# BLDController_v1_0.net
KiCad netlist of a schematic drawn in EAGLE
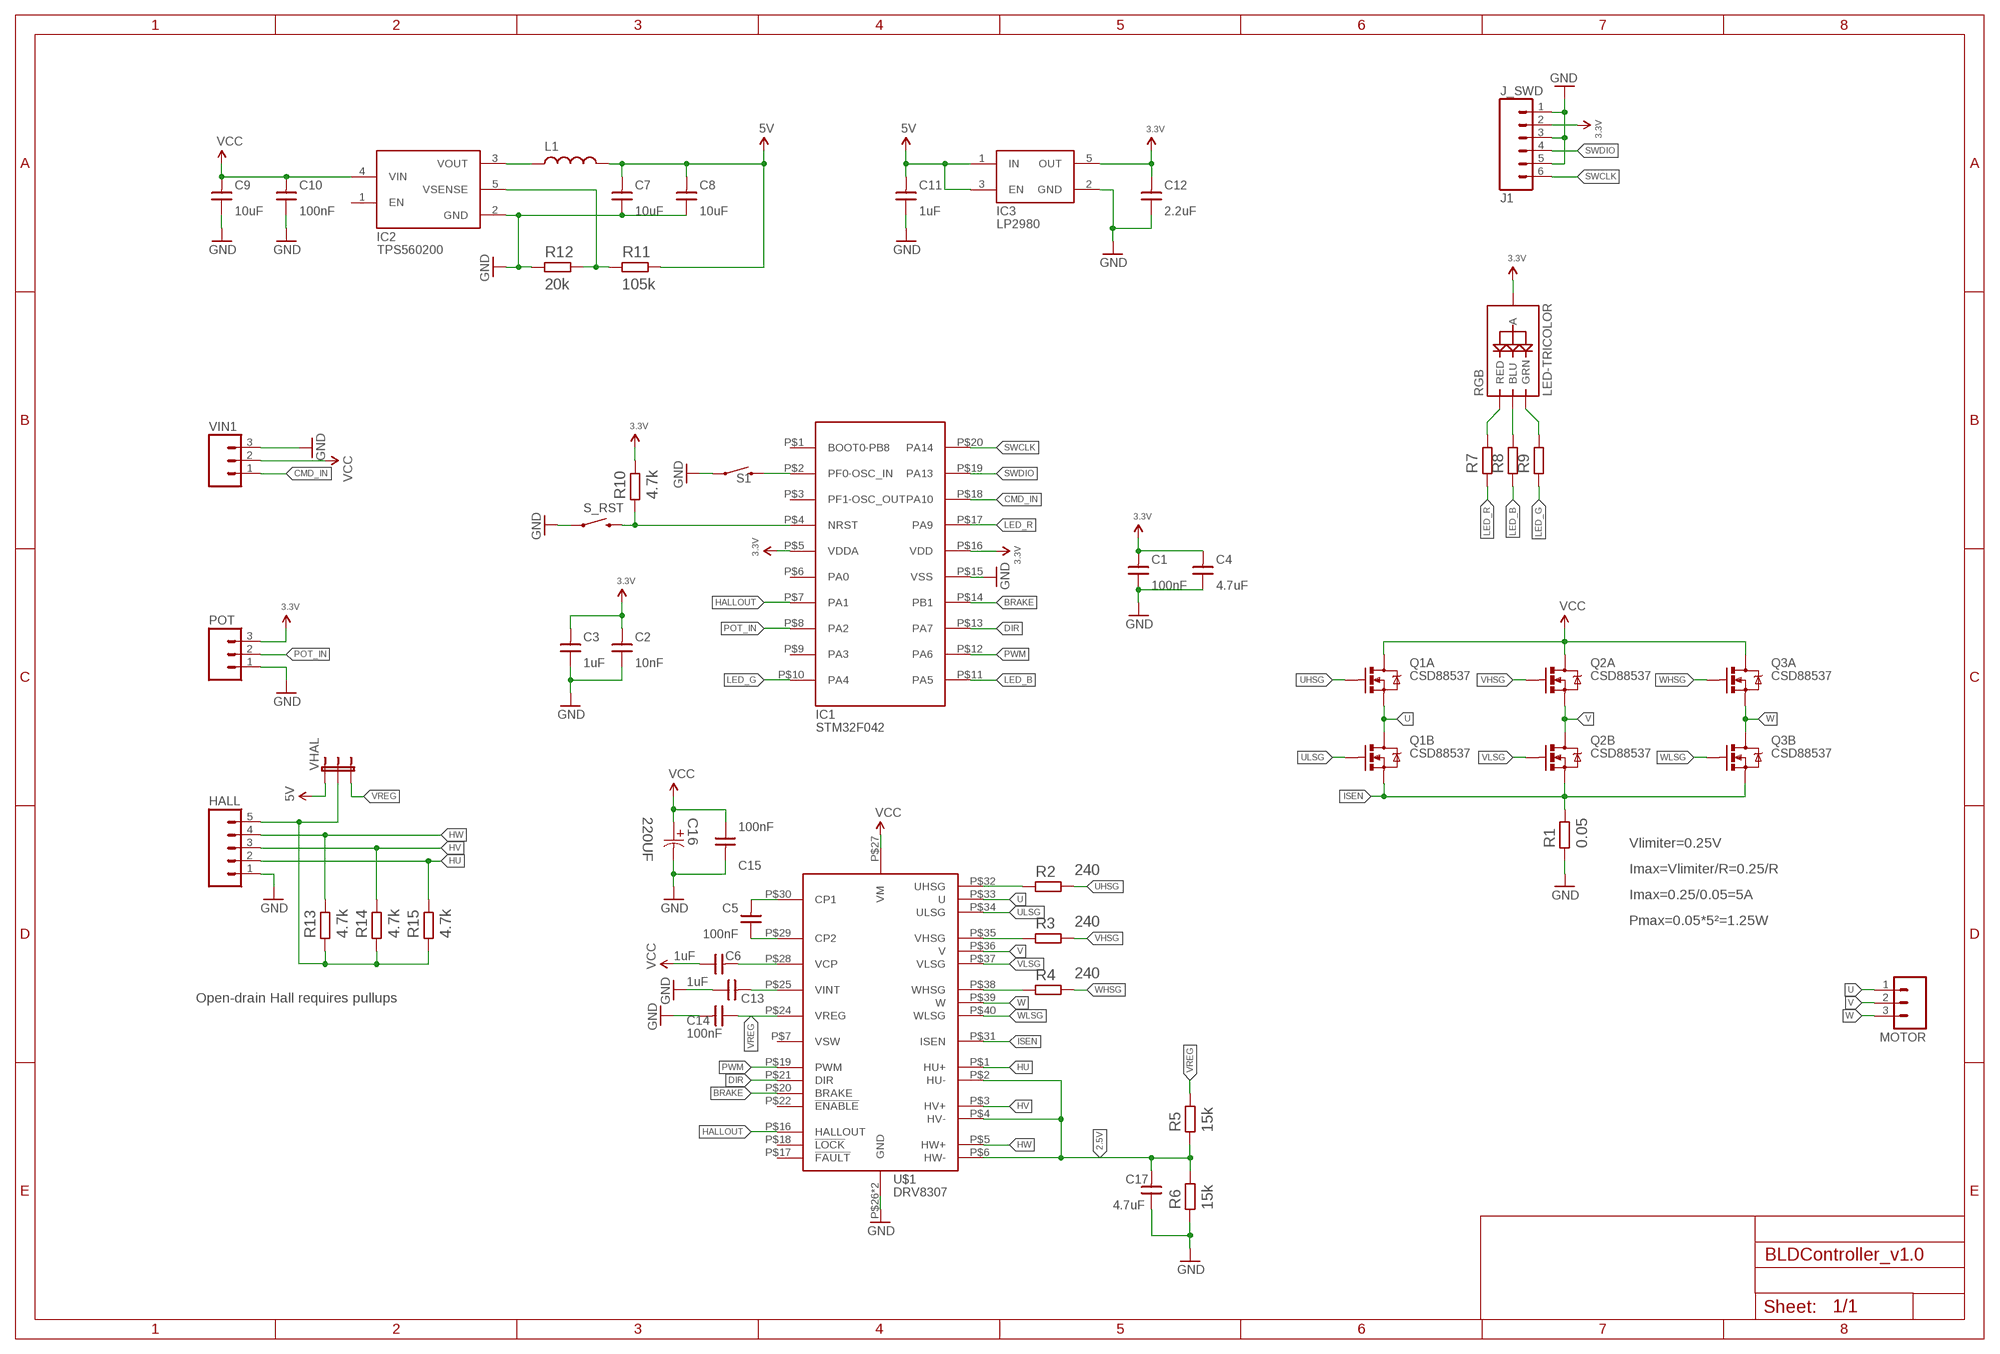
[diagram p0: schematic, sheet 1]

(export (version "E")
  (design (tool "Eeschema 10.0.6"))
  (components
    (comp (ref "C1")
      (value "100nF")
      (footprint "eagle-import:R0603")
      (libsource (lib "eagle-import") (part "C0603"))
    )
    (comp (ref "C2")
      (value "10nF")
      (footprint "eagle-import:R0603")
      (libsource (lib "eagle-import") (part "C0603"))
    )
    (comp (ref "C3")
      (value "1uF")
      (footprint "eagle-import:R0805")
      (libsource (lib "eagle-import") (part "C0805"))
    )
    (comp (ref "C4")
      (value "4.7uF")
      (footprint "eagle-import:R0805")
      (libsource (lib "eagle-import") (part "C0805"))
    )
    (comp (ref "C5")
      (value "100nF")
      (footprint "eagle-import:R0603")
      (libsource (lib "eagle-import") (part "C0603"))
    )
    (comp (ref "C6")
      (value "1uF")
      (footprint "eagle-import:R0805")
      (libsource (lib "eagle-import") (part "C0805"))
    )
    (comp (ref "C7")
      (value "10uF")
      (footprint "eagle-import:R0805")
      (libsource (lib "eagle-import") (part "C0805"))
    )
    (comp (ref "C8")
      (value "10uF")
      (footprint "eagle-import:R0805")
      (libsource (lib "eagle-import") (part "C0805"))
    )
    (comp (ref "C9")
      (value "10uF")
      (footprint "eagle-import:1206")
      (libsource (lib "eagle-import") (part "C1206"))
    )
    (comp (ref "C10")
      (value "100nF")
      (footprint "eagle-import:R0603")
      (libsource (lib "eagle-import") (part "C0603"))
    )
    (comp (ref "C11")
      (value "1uF")
      (footprint "eagle-import:R0805")
      (libsource (lib "eagle-import") (part "C0805"))
    )
    (comp (ref "C12")
      (value "2.2uF")
      (footprint "eagle-import:R0805")
      (libsource (lib "eagle-import") (part "C0805"))
    )
    (comp (ref "C13")
      (value "1uF")
      (footprint "eagle-import:R0805")
      (libsource (lib "eagle-import") (part "C0805"))
    )
    (comp (ref "C14")
      (value "100nF")
      (footprint "eagle-import:R0603")
      (libsource (lib "eagle-import") (part "C0603"))
    )
    (comp (ref "C15")
      (value "100nF")
      (footprint "eagle-import:R0603")
      (libsource (lib "eagle-import") (part "C0603"))
    )
    (comp (ref "C16")
      (value "220UF")
      (footprint "eagle-import:CAPPR500-1000X3200")
      (fields (field (name "MPN") "EEUFC1V221") (field (name "TOLERANCE") "±20 %"))
      (libsource (lib "eagle-import") (part "C_PANA-P5.0-D10FC1V221"))
    )
    (comp (ref "C17")
      (value "4.7uF")
      (footprint "eagle-import:R0603")
      (libsource (lib "eagle-import") (part "C0603"))
    )
    (comp (ref "HALL")
      (value "M05SCREW")
      (footprint "eagle-import:SCREWTERMINAL-3.5MM-5")
      (libsource (lib "eagle-import") (part "M05SCREW"))
    )
    (comp (ref "IC1")
      (value "STM32F042")
      (footprint "eagle-import:TSSOP20")
      (libsource (lib "eagle-import") (part "STM32F042"))
    )
    (comp (ref "IC2")
      (value "TPS560200")
      (footprint "eagle-import:SOT23-5L")
      (libsource (lib "eagle-import") (part "TPS560200"))
    )
    (comp (ref "IC3")
      (value "LP2980")
      (footprint "eagle-import:SOT23-5L")
      (libsource (lib "eagle-import") (part "LP2980"))
    )
    (comp (ref "J1")
      (value "J_SWD")
      (footprint "eagle-import:ZIF-06-1MM")
      (libsource (lib "eagle-import") (part "ZIF-06-1MM"))
    )
    (comp (ref "L1")
      (value "LNRG_4026")
      (footprint "eagle-import:NRG_4026")
      (libsource (lib "eagle-import") (part "LNRG_4026"))
    )
    (comp (ref "MOTOR")
      (value "M03-SCREW-5MM")
      (footprint "eagle-import:SCREWTERMINAL-5MM-3")
      (libsource (lib "eagle-import") (part "M03-SCREW-5MM"))
    )
    (comp (ref "POT")
      (value "M03SCREW")
      (footprint "eagle-import:SCREWTERMINAL-3.5MM-3")
      (libsource (lib "eagle-import") (part "M03SCREW"))
    )
    (comp (ref "Q1")
      (value "CSD88537")
      (footprint "eagle-import:SO-08")
      (libsource (lib "eagle-import") (part "CSD88537"))
    )
    (comp (ref "Q2")
      (value "CSD88537")
      (footprint "eagle-import:SO-08")
      (libsource (lib "eagle-import") (part "CSD88537"))
    )
    (comp (ref "Q3")
      (value "CSD88537")
      (footprint "eagle-import:SO-08")
      (libsource (lib "eagle-import") (part "CSD88537"))
    )
    (comp (ref "R1")
      (value "0.05")
      (footprint "eagle-import:CRF2512")
      (libsource (lib "eagle-import") (part "R2512"))
    )
    (comp (ref "R2")
      (value "240")
      (footprint "eagle-import:R0603")
      (libsource (lib "eagle-import") (part "R0603"))
    )
    (comp (ref "R3")
      (value "240")
      (footprint "eagle-import:R0603")
      (libsource (lib "eagle-import") (part "R0603"))
    )
    (comp (ref "R4")
      (value "240")
      (footprint "eagle-import:R0603")
      (libsource (lib "eagle-import") (part "R0603"))
    )
    (comp (ref "R5")
      (value "15k")
      (footprint "eagle-import:R0603")
      (libsource (lib "eagle-import") (part "R0603"))
    )
    (comp (ref "R6")
      (value "15k")
      (footprint "eagle-import:R0603")
      (libsource (lib "eagle-import") (part "R0603"))
    )
    (comp (ref "R7")
      (value "R0603")
      (footprint "eagle-import:R0603")
      (libsource (lib "eagle-import") (part "R0603"))
    )
    (comp (ref "R8")
      (value "R0603")
      (footprint "eagle-import:R0603")
      (libsource (lib "eagle-import") (part "R0603"))
    )
    (comp (ref "R9")
      (value "R0603")
      (footprint "eagle-import:R0603")
      (libsource (lib "eagle-import") (part "R0603"))
    )
    (comp (ref "R10")
      (value "4.7k")
      (footprint "eagle-import:R0603")
      (libsource (lib "eagle-import") (part "R0603"))
    )
    (comp (ref "R11")
      (value "105k")
      (footprint "eagle-import:R0603")
      (libsource (lib "eagle-import") (part "R0603"))
    )
    (comp (ref "R12")
      (value "20k")
      (footprint "eagle-import:R0603")
      (libsource (lib "eagle-import") (part "R0603"))
    )
    (comp (ref "R13")
      (value "4.7k")
      (footprint "eagle-import:R0603")
      (libsource (lib "eagle-import") (part "R0603"))
    )
    (comp (ref "R14")
      (value "4.7k")
      (footprint "eagle-import:R0603")
      (libsource (lib "eagle-import") (part "R0603"))
    )
    (comp (ref "R15")
      (value "4.7k")
      (footprint "eagle-import:R0603")
      (libsource (lib "eagle-import") (part "R0603"))
    )
    (comp (ref "RGB")
      (value "LED-TRICOLOR")
      (footprint "eagle-import:PLCC4")
      (libsource (lib "eagle-import") (part "LED-TRICOLOR"))
    )
    (comp (ref "S1")
      (value "SWITCH-MOMENTARY-2SMD-3")
      (footprint "eagle-import:TACTILE_SWITCH_SMD-3")
      (libsource (lib "eagle-import") (part "SWITCH-MOMENTARY-2SMD-3"))
    )
    (comp (ref "S_RST")
      (value "SWITCH-MOMENTARY-2SMD-3")
      (footprint "eagle-import:TACTILE_SWITCH_SMD-3")
      (libsource (lib "eagle-import") (part "SWITCH-MOMENTARY-2SMD-3"))
    )
    (comp (ref "U$1")
      (value "DRV8307")
      (footprint "eagle-import:PVQFN-N40")
      (libsource (lib "eagle-import") (part "DRV8307"))
    )
    (comp (ref "VHAL")
      (value "JUMPER-3SMD")
      (footprint "eagle-import:SJ_3")
      (libsource (lib "eagle-import") (part "JUMPER-3SMD"))
    )
    (comp (ref "VIN1")
      (value "M03SCREW")
      (footprint "eagle-import:SCREWTERMINAL-3.5MM-3")
      (libsource (lib "eagle-import") (part "M03SCREW"))
    )
  )
  (nets
    (net (code "1") (name "2.5V") (class "Default")
      (node (ref "C17") (pin "2") (pinfunction "2_2") (pintype "bidirectional"))
      (node (ref "R5") (pin "1") (pinfunction "1_1") (pintype "bidirectional"))
      (node (ref "R6") (pin "2") (pinfunction "2_2") (pintype "bidirectional"))
      (node (ref "U$1") (pin "P$2") (pinfunction "HU-_P$2") (pintype "bidirectional"))
      (node (ref "U$1") (pin "P$4") (pinfunction "HV-_P$4") (pintype "bidirectional"))
      (node (ref "U$1") (pin "P$6") (pinfunction "HW-_P$6") (pintype "bidirectional"))
    )
    (net (code "2") (name "3.3V") (class "Default")
      (node (ref "C1") (pin "2") (pinfunction "2_2") (pintype "bidirectional"))
      (node (ref "C12") (pin "2") (pinfunction "2_2") (pintype "bidirectional"))
      (node (ref "C2") (pin "2") (pinfunction "2_2") (pintype "bidirectional"))
      (node (ref "C3") (pin "2") (pinfunction "2_2") (pintype "bidirectional"))
      (node (ref "C4") (pin "2") (pinfunction "2_2") (pintype "bidirectional"))
      (node (ref "IC1") (pin "P$16") (pinfunction "VDD_P$16") (pintype "bidirectional"))
      (node (ref "IC1") (pin "P$5") (pinfunction "VDDA_P$5") (pintype "bidirectional"))
      (node (ref "IC3") (pin "5") (pinfunction "OUT_5") (pintype "bidirectional"))
      (node (ref "J1") (pin "2") (pinfunction "2_2") (pintype "passive"))
      (node (ref "POT") (pin "3") (pinfunction "3_3") (pintype "passive"))
      (node (ref "R10") (pin "2") (pinfunction "2_2") (pintype "bidirectional"))
      (node (ref "RGB") (pin "P$1") (pinfunction "A_P$1") (pintype "bidirectional"))
    )
    (net (code "3") (name "5V") (class "Default")
      (node (ref "C11") (pin "2") (pinfunction "2_2") (pintype "bidirectional"))
      (node (ref "C7") (pin "2") (pinfunction "2_2") (pintype "bidirectional"))
      (node (ref "C8") (pin "2") (pinfunction "2_2") (pintype "bidirectional"))
      (node (ref "IC3") (pin "1") (pinfunction "IN_1") (pintype "bidirectional"))
      (node (ref "IC3") (pin "3") (pinfunction "EN_3") (pintype "bidirectional"))
      (node (ref "L1") (pin "P$2") (pinfunction "2_P$2") (pintype "bidirectional"))
      (node (ref "R11") (pin "2") (pinfunction "2_2") (pintype "bidirectional"))
      (node (ref "VHAL") (pin "1") (pinfunction "1_1") (pintype "passive"))
    )
    (net (code "4") (name "BRAKE") (class "Default")
      (node (ref "IC1") (pin "P$14") (pinfunction "PB1_P$14") (pintype "bidirectional"))
      (node (ref "U$1") (pin "P$20") (pinfunction "BRAKE_P$20") (pintype "bidirectional"))
    )
    (net (code "5") (name "CMD_IN") (class "Default")
      (node (ref "IC1") (pin "P$18") (pinfunction "PA10_P$18") (pintype "bidirectional"))
      (node (ref "VIN1") (pin "1") (pinfunction "1_1") (pintype "passive"))
    )
    (net (code "6") (name "DIR") (class "Default")
      (node (ref "IC1") (pin "P$13") (pinfunction "PA7_P$13") (pintype "bidirectional"))
      (node (ref "U$1") (pin "P$21") (pinfunction "DIR_P$21") (pintype "bidirectional"))
    )
    (net (code "7") (name "GND") (class "Default")
      (node (ref "C1") (pin "1") (pinfunction "1_1") (pintype "bidirectional"))
      (node (ref "C10") (pin "1") (pinfunction "1_1") (pintype "bidirectional"))
      (node (ref "C11") (pin "1") (pinfunction "1_1") (pintype "bidirectional"))
      (node (ref "C12") (pin "1") (pinfunction "1_1") (pintype "bidirectional"))
      (node (ref "C13") (pin "1") (pinfunction "1_1") (pintype "bidirectional"))
      (node (ref "C14") (pin "2") (pinfunction "2_2") (pintype "bidirectional"))
      (node (ref "C15") (pin "2") (pinfunction "2_2") (pintype "bidirectional"))
      (node (ref "C16") (pin "2") (pinfunction "2_2") (pintype "passive"))
      (node (ref "C17") (pin "1") (pinfunction "1_1") (pintype "bidirectional"))
      (node (ref "C2") (pin "1") (pinfunction "1_1") (pintype "bidirectional"))
      (node (ref "C3") (pin "1") (pinfunction "1_1") (pintype "bidirectional"))
      (node (ref "C4") (pin "1") (pinfunction "1_1") (pintype "bidirectional"))
      (node (ref "C7") (pin "1") (pinfunction "1_1") (pintype "bidirectional"))
      (node (ref "C8") (pin "1") (pinfunction "1_1") (pintype "bidirectional"))
      (node (ref "C9") (pin "1") (pinfunction "1_1") (pintype "bidirectional"))
      (node (ref "HALL") (pin "1") (pinfunction "1_1") (pintype "passive"))
      (node (ref "IC1") (pin "P$15") (pinfunction "VSS_P$15") (pintype "bidirectional"))
      (node (ref "IC2") (pin "2") (pinfunction "GND_2") (pintype "bidirectional"))
      (node (ref "IC3") (pin "2") (pinfunction "GND_2") (pintype "bidirectional"))
      (node (ref "J1") (pin "1") (pinfunction "1_1") (pintype "passive"))
      (node (ref "J1") (pin "3") (pinfunction "3_3") (pintype "passive"))
      (node (ref "J1") (pin "5") (pinfunction "5_5") (pintype "passive"))
      (node (ref "POT") (pin "1") (pinfunction "1_1") (pintype "passive"))
      (node (ref "R1") (pin "P$1") (pinfunction "1_P$1") (pintype "bidirectional"))
      (node (ref "R12") (pin "1") (pinfunction "1_1") (pintype "bidirectional"))
      (node (ref "R6") (pin "1") (pinfunction "1_1") (pintype "bidirectional"))
      (node (ref "S1") (pin "1") (pinfunction "1_1") (pintype "passive"))
      (node (ref "S_RST") (pin "1") (pinfunction "1_1") (pintype "passive"))
      (node (ref "U$1") (pin "P$26") (pinfunction "GND_P$26") (pintype "bidirectional"))
      (node (ref "U$1") (pin "PAD") (pinfunction "GND_PAD") (pintype "bidirectional"))
      (node (ref "VIN1") (pin "3") (pinfunction "3_3") (pintype "passive"))
    )
    (net (code "8") (name "HALLOUT") (class "Default")
      (node (ref "IC1") (pin "P$7") (pinfunction "PA1_P$7") (pintype "bidirectional"))
      (node (ref "U$1") (pin "P$16") (pinfunction "HALLOUT_P$16") (pintype "bidirectional"))
    )
    (net (code "9") (name "HU") (class "Default")
      (node (ref "HALL") (pin "2") (pinfunction "2_2") (pintype "passive"))
      (node (ref "R15") (pin "2") (pinfunction "2_2") (pintype "bidirectional"))
      (node (ref "U$1") (pin "P$1") (pinfunction "HU+_P$1") (pintype "bidirectional"))
    )
    (net (code "10") (name "HV") (class "Default")
      (node (ref "HALL") (pin "3") (pinfunction "3_3") (pintype "passive"))
      (node (ref "R14") (pin "2") (pinfunction "2_2") (pintype "bidirectional"))
      (node (ref "U$1") (pin "P$3") (pinfunction "HV+_P$3") (pintype "bidirectional"))
    )
    (net (code "11") (name "HW") (class "Default")
      (node (ref "HALL") (pin "4") (pinfunction "4_4") (pintype "passive"))
      (node (ref "R13") (pin "2") (pinfunction "2_2") (pintype "bidirectional"))
      (node (ref "U$1") (pin "P$5") (pinfunction "HW+_P$5") (pintype "bidirectional"))
    )
    (net (code "12") (name "ISEN") (class "Default")
      (node (ref "Q1") (pin "3") (pinfunction "S_3") (pintype "passive"))
      (node (ref "Q2") (pin "3") (pinfunction "S_3") (pintype "passive"))
      (node (ref "Q3") (pin "3") (pinfunction "S_3") (pintype "passive"))
      (node (ref "R1") (pin "P$2") (pinfunction "2_P$2") (pintype "bidirectional"))
      (node (ref "U$1") (pin "P$31") (pinfunction "ISEN_P$31") (pintype "bidirectional"))
    )
    (net (code "13") (name "LED_B") (class "Default")
      (node (ref "IC1") (pin "P$11") (pinfunction "PA5_P$11") (pintype "bidirectional"))
      (node (ref "R8") (pin "1") (pinfunction "1_1") (pintype "bidirectional"))
    )
    (net (code "14") (name "LED_G") (class "Default")
      (node (ref "IC1") (pin "P$10") (pinfunction "PA4_P$10") (pintype "bidirectional"))
      (node (ref "R9") (pin "1") (pinfunction "1_1") (pintype "bidirectional"))
    )
    (net (code "15") (name "LED_R") (class "Default")
      (node (ref "IC1") (pin "P$17") (pinfunction "PA9_P$17") (pintype "bidirectional"))
      (node (ref "R7") (pin "1") (pinfunction "1_1") (pintype "bidirectional"))
    )
    (net (code "16") (name "Net-(HALL-Pad5)") (class "Default")
      (node (ref "HALL") (pin "5") (pinfunction "5_5") (pintype "passive"))
      (node (ref "R13") (pin "1") (pinfunction "1_1") (pintype "bidirectional"))
      (node (ref "R14") (pin "1") (pinfunction "1_1") (pintype "bidirectional"))
      (node (ref "R15") (pin "1") (pinfunction "1_1") (pintype "bidirectional"))
      (node (ref "VHAL") (pin "2") (pinfunction "2_2") (pintype "passive"))
    )
    (net (code "17") (name "Net-(IC1-NRST)") (class "Default")
      (node (ref "IC1") (pin "P$4") (pinfunction "NRST_P$4") (pintype "bidirectional"))
      (node (ref "R10") (pin "1") (pinfunction "1_1") (pintype "bidirectional"))
      (node (ref "S_RST") (pin "4") (pinfunction "2_4") (pintype "passive"))
    )
    (net (code "18") (name "Net-(IC1-PF0-OSC_IN)") (class "Default")
      (node (ref "IC1") (pin "P$2") (pinfunction "PF0-OSC_IN_P$2") (pintype "bidirectional"))
      (node (ref "S1") (pin "4") (pinfunction "2_4") (pintype "passive"))
    )
    (net (code "19") (name "Net-(IC2-VOUT)") (class "Default")
      (node (ref "IC2") (pin "3") (pinfunction "VOUT_3") (pintype "bidirectional"))
      (node (ref "L1") (pin "P$1") (pinfunction "1_P$1") (pintype "bidirectional"))
    )
    (net (code "20") (name "Net-(IC2-VSENSE)") (class "Default")
      (node (ref "IC2") (pin "5") (pinfunction "VSENSE_5") (pintype "bidirectional"))
      (node (ref "R11") (pin "1") (pinfunction "1_1") (pintype "bidirectional"))
      (node (ref "R12") (pin "2") (pinfunction "2_2") (pintype "bidirectional"))
    )
    (net (code "21") (name "Net-(RGB-BLU)") (class "Default")
      (node (ref "R8") (pin "2") (pinfunction "2_2") (pintype "bidirectional"))
      (node (ref "RGB") (pin "P$2") (pinfunction "BLU_P$2") (pintype "bidirectional"))
    )
    (net (code "22") (name "Net-(RGB-GRN)") (class "Default")
      (node (ref "R9") (pin "2") (pinfunction "2_2") (pintype "bidirectional"))
      (node (ref "RGB") (pin "P$3") (pinfunction "GRN_P$3") (pintype "bidirectional"))
    )
    (net (code "23") (name "Net-(RGB-RED)") (class "Default")
      (node (ref "R7") (pin "2") (pinfunction "2_2") (pintype "bidirectional"))
      (node (ref "RGB") (pin "P$4") (pinfunction "RED_P$4") (pintype "bidirectional"))
    )
    (net (code "24") (name "Net-(U$1-CP1)") (class "Default")
      (node (ref "C5") (pin "2") (pinfunction "2_2") (pintype "bidirectional"))
      (node (ref "U$1") (pin "P$30") (pinfunction "CP1_P$30") (pintype "bidirectional"))
    )
    (net (code "25") (name "Net-(U$1-CP2)") (class "Default")
      (node (ref "C5") (pin "1") (pinfunction "1_1") (pintype "bidirectional"))
      (node (ref "U$1") (pin "P$29") (pinfunction "CP2_P$29") (pintype "bidirectional"))
    )
    (net (code "26") (name "Net-(U$1-UHSG)") (class "Default")
      (node (ref "R2") (pin "1") (pinfunction "1_1") (pintype "bidirectional"))
      (node (ref "U$1") (pin "P$32") (pinfunction "UHSG_P$32") (pintype "bidirectional"))
    )
    (net (code "27") (name "Net-(U$1-VCP)") (class "Default")
      (node (ref "C6") (pin "2") (pinfunction "2_2") (pintype "bidirectional"))
      (node (ref "U$1") (pin "P$28") (pinfunction "VCP_P$28") (pintype "bidirectional"))
    )
    (net (code "28") (name "Net-(U$1-VHSG)") (class "Default")
      (node (ref "R3") (pin "1") (pinfunction "1_1") (pintype "bidirectional"))
      (node (ref "U$1") (pin "P$35") (pinfunction "VHSG_P$35") (pintype "bidirectional"))
    )
    (net (code "29") (name "Net-(U$1-VINT)") (class "Default")
      (node (ref "C13") (pin "2") (pinfunction "2_2") (pintype "bidirectional"))
      (node (ref "U$1") (pin "P$25") (pinfunction "VINT_P$25") (pintype "bidirectional"))
    )
    (net (code "30") (name "Net-(U$1-WHSG)") (class "Default")
      (node (ref "R4") (pin "1") (pinfunction "1_1") (pintype "bidirectional"))
      (node (ref "U$1") (pin "P$38") (pinfunction "WHSG_P$38") (pintype "bidirectional"))
    )
    (net (code "31") (name "POT_IN") (class "Default")
      (node (ref "IC1") (pin "P$8") (pinfunction "PA2_P$8") (pintype "bidirectional"))
      (node (ref "POT") (pin "2") (pinfunction "2_2") (pintype "passive"))
    )
    (net (code "32") (name "PWM") (class "Default")
      (node (ref "IC1") (pin "P$12") (pinfunction "PA6_P$12") (pintype "bidirectional"))
      (node (ref "U$1") (pin "P$19") (pinfunction "PWM_P$19") (pintype "bidirectional"))
    )
    (net (code "33") (name "SWCLK") (class "Default")
      (node (ref "IC1") (pin "P$20") (pinfunction "PA14_P$20") (pintype "bidirectional"))
      (node (ref "J1") (pin "6") (pinfunction "6_6") (pintype "passive"))
    )
    (net (code "34") (name "SWDIO") (class "Default")
      (node (ref "IC1") (pin "P$19") (pinfunction "PA13_P$19") (pintype "bidirectional"))
      (node (ref "J1") (pin "4") (pinfunction "4_4") (pintype "passive"))
    )
    (net (code "35") (name "U") (class "Default")
      (node (ref "MOTOR") (pin "1") (pinfunction "1_1") (pintype "passive"))
      (node (ref "Q1") (pin "1") (pinfunction "S_1") (pintype "passive"))
      (node (ref "Q1") (pin "5") (pinfunction "D_5") (pintype "passive"))
      (node (ref "Q1") (pin "6") (pinfunction "D_6") (pintype "passive"))
      (node (ref "U$1") (pin "P$33") (pinfunction "U_P$33") (pintype "bidirectional"))
    )
    (net (code "36") (name "UHSG") (class "Default")
      (node (ref "Q1") (pin "2") (pinfunction "G_2") (pintype "passive"))
      (node (ref "R2") (pin "2") (pinfunction "2_2") (pintype "bidirectional"))
    )
    (net (code "37") (name "ULSG") (class "Default")
      (node (ref "Q1") (pin "4") (pinfunction "G_4") (pintype "passive"))
      (node (ref "U$1") (pin "P$34") (pinfunction "ULSG_P$34") (pintype "bidirectional"))
    )
    (net (code "38") (name "V") (class "Default")
      (node (ref "MOTOR") (pin "2") (pinfunction "2_2") (pintype "passive"))
      (node (ref "Q2") (pin "1") (pinfunction "S_1") (pintype "passive"))
      (node (ref "Q2") (pin "5") (pinfunction "D_5") (pintype "passive"))
      (node (ref "Q2") (pin "6") (pinfunction "D_6") (pintype "passive"))
      (node (ref "U$1") (pin "P$36") (pinfunction "V_P$36") (pintype "bidirectional"))
    )
    (net (code "39") (name "VCC") (class "Default")
      (node (ref "C10") (pin "2") (pinfunction "2_2") (pintype "bidirectional"))
      (node (ref "C15") (pin "1") (pinfunction "1_1") (pintype "bidirectional"))
      (node (ref "C16") (pin "1") (pinfunction "1_1") (pintype "passive"))
      (node (ref "C6") (pin "1") (pinfunction "1_1") (pintype "bidirectional"))
      (node (ref "C9") (pin "2") (pinfunction "2_2") (pintype "bidirectional"))
      (node (ref "IC2") (pin "4") (pinfunction "VIN_4") (pintype "bidirectional"))
      (node (ref "Q1") (pin "7") (pinfunction "D_7") (pintype "passive"))
      (node (ref "Q1") (pin "8") (pinfunction "D_8") (pintype "passive"))
      (node (ref "Q2") (pin "7") (pinfunction "D_7") (pintype "passive"))
      (node (ref "Q2") (pin "8") (pinfunction "D_8") (pintype "passive"))
      (node (ref "Q3") (pin "7") (pinfunction "D_7") (pintype "passive"))
      (node (ref "Q3") (pin "8") (pinfunction "D_8") (pintype "passive"))
      (node (ref "U$1") (pin "P$27") (pinfunction "VM_P$27") (pintype "bidirectional"))
      (node (ref "VIN1") (pin "2") (pinfunction "2_2") (pintype "passive"))
    )
    (net (code "40") (name "VHSG") (class "Default")
      (node (ref "Q2") (pin "2") (pinfunction "G_2") (pintype "passive"))
      (node (ref "R3") (pin "2") (pinfunction "2_2") (pintype "bidirectional"))
    )
    (net (code "41") (name "VLSG") (class "Default")
      (node (ref "Q2") (pin "4") (pinfunction "G_4") (pintype "passive"))
      (node (ref "U$1") (pin "P$37") (pinfunction "VLSG_P$37") (pintype "bidirectional"))
    )
    (net (code "42") (name "VREG") (class "Default")
      (node (ref "C14") (pin "1") (pinfunction "1_1") (pintype "bidirectional"))
      (node (ref "R5") (pin "2") (pinfunction "2_2") (pintype "bidirectional"))
      (node (ref "U$1") (pin "P$24") (pinfunction "VREG_P$24") (pintype "bidirectional"))
      (node (ref "VHAL") (pin "3") (pinfunction "3_3") (pintype "passive"))
    )
    (net (code "43") (name "W") (class "Default")
      (node (ref "MOTOR") (pin "3") (pinfunction "3_3") (pintype "passive"))
      (node (ref "Q3") (pin "1") (pinfunction "S_1") (pintype "passive"))
      (node (ref "Q3") (pin "5") (pinfunction "D_5") (pintype "passive"))
      (node (ref "Q3") (pin "6") (pinfunction "D_6") (pintype "passive"))
      (node (ref "U$1") (pin "P$39") (pinfunction "W_P$39") (pintype "bidirectional"))
    )
    (net (code "44") (name "WHSG") (class "Default")
      (node (ref "Q3") (pin "2") (pinfunction "G_2") (pintype "passive"))
      (node (ref "R4") (pin "2") (pinfunction "2_2") (pintype "bidirectional"))
    )
    (net (code "45") (name "WLSG") (class "Default")
      (node (ref "Q3") (pin "4") (pinfunction "G_4") (pintype "passive"))
      (node (ref "U$1") (pin "P$40") (pinfunction "WLSG_P$40") (pintype "bidirectional"))
    )
    (net (code "46") (name "unconnected-(IC1-BOOT0-PB8-PadP$1)") (class "Default")
      (node (ref "IC1") (pin "P$1") (pinfunction "BOOT0-PB8_P$1") (pintype "bidirectional"))
    )
    (net (code "47") (name "unconnected-(IC1-PA0-PadP$6)") (class "Default")
      (node (ref "IC1") (pin "P$6") (pinfunction "PA0_P$6") (pintype "bidirectional"))
    )
    (net (code "48") (name "unconnected-(IC1-PA3-PadP$9)") (class "Default")
      (node (ref "IC1") (pin "P$9") (pinfunction "PA3_P$9") (pintype "bidirectional"))
    )
    (net (code "49") (name "unconnected-(IC1-PF1-OSC_OUT-PadP$3)") (class "Default")
      (node (ref "IC1") (pin "P$3") (pinfunction "PF1-OSC_OUT_P$3") (pintype "bidirectional"))
    )
    (net (code "50") (name "unconnected-(IC2-EN-Pad1)") (class "Default")
      (node (ref "IC2") (pin "1") (pinfunction "EN_1") (pintype "bidirectional"))
    )
    (net (code "51") (name "unconnected-(U$1-VSW-PadP$7)") (class "Default")
      (node (ref "U$1") (pin "P$7") (pinfunction "VSW_P$7") (pintype "bidirectional"))
    )
    (net (code "52") (name "unconnected-(U$1-~{ENABLE}-PadP$22)") (class "Default")
      (node (ref "U$1") (pin "P$22") (pinfunction "~{ENABLE}_P$22") (pintype "bidirectional"))
    )
    (net (code "53") (name "unconnected-(U$1-~{FAULT}-PadP$17)") (class "Default")
      (node (ref "U$1") (pin "P$17") (pinfunction "~{FAULT}_P$17") (pintype "bidirectional"))
    )
    (net (code "54") (name "unconnected-(U$1-~{LOCK}-PadP$18)") (class "Default")
      (node (ref "U$1") (pin "P$18") (pinfunction "~{LOCK}_P$18") (pintype "bidirectional"))
    )
  )
)
